# hss-mag-enc-v1.net
KiCad netlist of a schematic drawn in EAGLE
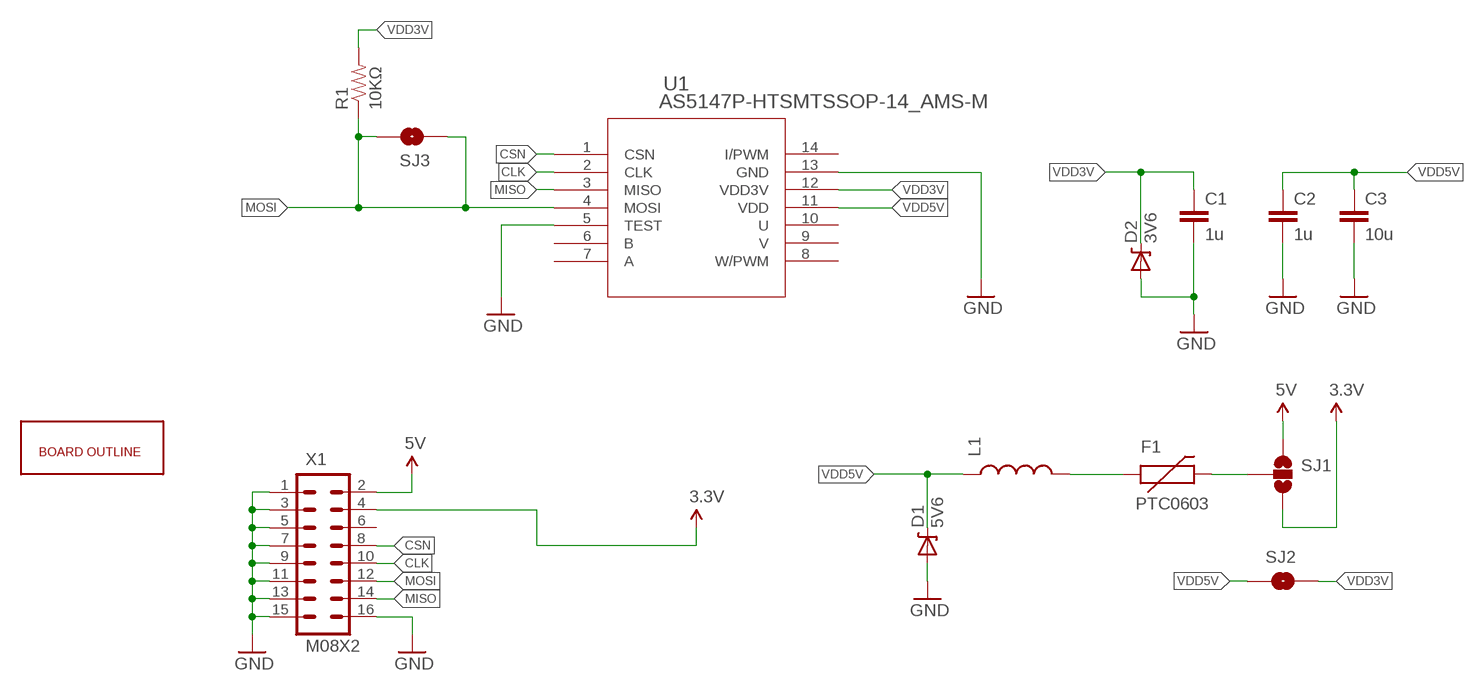
[diagram p0: schematic, sheet 1]

(export (version "E")
  (design (tool "Eeschema 10.0.6"))
  (components
    (comp (ref "C1")
      (value "1u")
      (footprint "eagle-import:0805")
      (libsource (lib "eagle-import") (part "CAP0805"))
    )
    (comp (ref "C2")
      (value "1u")
      (footprint "eagle-import:0805")
      (libsource (lib "eagle-import") (part "CAP0805"))
    )
    (comp (ref "C3")
      (value "10u")
      (footprint "eagle-import:0805")
      (libsource (lib "eagle-import") (part "CAP0805"))
    )
    (comp (ref "D1")
      (value "5V6")
      (footprint "eagle-import:SOD-323")
      (libsource (lib "eagle-import") (part "DIODE-ZENER-BZT52"))
    )
    (comp (ref "D2")
      (value "3V6")
      (footprint "eagle-import:SOD-323")
      (libsource (lib "eagle-import") (part "DIODE-ZENER-BZT52"))
    )
    (comp (ref "F1")
      (value "PTC0603")
      (footprint "eagle-import:0603")
      (libsource (lib "eagle-import") (part "PTC0603"))
    )
    (comp (ref "L1")
      (value "INDUCTOR0805")
      (footprint "eagle-import:0805")
      (libsource (lib "eagle-import") (part "INDUCTOR0805"))
    )
    (comp (ref "R1")
      (value "10KΩ")
      (footprint "eagle-import:0603-RES")
      (libsource (lib "eagle-import") (part "RESISTOR0603-RES"))
    )
    (comp (ref "SJ1")
      (value "SOLDERJUMPER_2WAYS")
      (footprint "eagle-import:SJ_3")
      (libsource (lib "eagle-import") (part "SOLDERJUMPER_2WAYS"))
    )
    (comp (ref "SJ2")
      (value "SOLDERJUMPERNO")
      (footprint "eagle-import:SJ_2S-NO")
      (libsource (lib "eagle-import") (part "SOLDERJUMPERNO"))
    )
    (comp (ref "SJ3")
      (value "SOLDERJUMPERNO")
      (footprint "eagle-import:SJ_2S-NO")
      (libsource (lib "eagle-import") (part "SOLDERJUMPERNO"))
    )
    (comp (ref "U$1")
      (value "BOARD-OUTLINE-V1")
      (footprint "eagle-import:BOARD-OUTLINE")
      (libsource (lib "eagle-import") (part "BOARD-OUTLINE-V1"))
    )
    (comp (ref "U1")
      (value "AS5147P-HTSMTSSOP-14_AMS-M")
      (footprint "eagle-import:TSSOP-14_AMS-M")
      (fields
        (field (name "MANUFACTURER_PART_NUMBER") "AS5147P-HTSM")
        (field (name "COPYRIGHT") "Copyright (C) 2025 Ultra Librarian. All rights reserved.")
      )
      (libsource (lib "eagle-import") (part "AS5147P-HTSMTSSOP-14_AMS-M"))
    )
    (comp (ref "X1")
      (value "M08X2")
      (footprint "eagle-import:2X8")
      (libsource (lib "eagle-import") (part "M08X2"))
    )
  )
  (nets
    (net (code "1") (name "3.3V") (class "Default")
      (node (ref "SJ1") (pin "3") (pinfunction "3_3") (pintype "passive"))
      (node (ref "X1") (pin "4") (pinfunction "4_4") (pintype "passive"))
    )
    (net (code "2") (name "5V") (class "Default")
      (node (ref "SJ1") (pin "1") (pinfunction "1_1") (pintype "passive"))
      (node (ref "X1") (pin "2") (pinfunction "2_2") (pintype "passive"))
    )
    (net (code "3") (name "CLK") (class "Default")
      (node (ref "U1") (pin "2") (pinfunction "CLK_2") (pintype "input"))
      (node (ref "X1") (pin "10") (pinfunction "10_10") (pintype "passive"))
    )
    (net (code "4") (name "CSN") (class "Default")
      (node (ref "U1") (pin "1") (pinfunction "CSN_1") (pintype "input"))
      (node (ref "X1") (pin "8") (pinfunction "8_8") (pintype "passive"))
    )
    (net (code "5") (name "GND") (class "Default")
      (node (ref "C1") (pin "2") (pinfunction "2_2") (pintype "passive"))
      (node (ref "C2") (pin "2") (pinfunction "2_2") (pintype "passive"))
      (node (ref "C3") (pin "2") (pinfunction "2_2") (pintype "passive"))
      (node (ref "D1") (pin "2") (pinfunction "A_2") (pintype "passive"))
      (node (ref "D2") (pin "2") (pinfunction "A_2") (pintype "passive"))
      (node (ref "U1") (pin "13") (pinfunction "GND_13") (pintype "passive"))
      (node (ref "U1") (pin "5") (pinfunction "TEST_5") (pintype "passive"))
      (node (ref "X1") (pin "1") (pinfunction "1_1") (pintype "passive"))
      (node (ref "X1") (pin "11") (pinfunction "11_11") (pintype "passive"))
      (node (ref "X1") (pin "13") (pinfunction "13_13") (pintype "passive"))
      (node (ref "X1") (pin "15") (pinfunction "15_15") (pintype "passive"))
      (node (ref "X1") (pin "16") (pinfunction "16_16") (pintype "passive"))
      (node (ref "X1") (pin "3") (pinfunction "3_3") (pintype "passive"))
      (node (ref "X1") (pin "5") (pinfunction "5_5") (pintype "passive"))
      (node (ref "X1") (pin "7") (pinfunction "7_7") (pintype "passive"))
      (node (ref "X1") (pin "9") (pinfunction "9_9") (pintype "passive"))
    )
    (net (code "6") (name "MISO") (class "Default")
      (node (ref "U1") (pin "3") (pinfunction "MISO_3") (pintype "output"))
      (node (ref "X1") (pin "14") (pinfunction "14_14") (pintype "passive"))
    )
    (net (code "7") (name "MOSI") (class "Default")
      (node (ref "R1") (pin "1") (pinfunction "1_1") (pintype "passive"))
      (node (ref "SJ3") (pin "1") (pinfunction "1_1") (pintype "passive"))
      (node (ref "SJ3") (pin "2") (pinfunction "2_2") (pintype "passive"))
      (node (ref "U1") (pin "4") (pinfunction "MOSI_4") (pintype "input"))
      (node (ref "X1") (pin "12") (pinfunction "12_12") (pintype "passive"))
    )
    (net (code "8") (name "Net-(F1-Pad1)") (class "Default")
      (node (ref "F1") (pin "1") (pinfunction "1_1") (pintype "bidirectional"))
      (node (ref "L1") (pin "2") (pinfunction "2_2") (pintype "passive"))
    )
    (net (code "9") (name "Net-(F1-Pad2)") (class "Default")
      (node (ref "F1") (pin "2") (pinfunction "2_2") (pintype "bidirectional"))
      (node (ref "SJ1") (pin "2") (pinfunction "2_2") (pintype "passive"))
    )
    (net (code "10") (name "VDD3V") (class "Default")
      (node (ref "C1") (pin "1") (pinfunction "1_1") (pintype "passive"))
      (node (ref "D2") (pin "1") (pinfunction "C_1") (pintype "passive"))
      (node (ref "R1") (pin "2") (pinfunction "2_2") (pintype "passive"))
      (node (ref "SJ2") (pin "2") (pinfunction "2_2") (pintype "passive"))
      (node (ref "U1") (pin "12") (pinfunction "VDD3V_12") (pintype "power_in"))
    )
    (net (code "11") (name "VDD5V") (class "Default")
      (node (ref "C2") (pin "1") (pinfunction "1_1") (pintype "passive"))
      (node (ref "C3") (pin "1") (pinfunction "1_1") (pintype "passive"))
      (node (ref "D1") (pin "1") (pinfunction "C_1") (pintype "passive"))
      (node (ref "L1") (pin "1") (pinfunction "1_1") (pintype "passive"))
      (node (ref "SJ2") (pin "1") (pinfunction "1_1") (pintype "passive"))
      (node (ref "U1") (pin "11") (pinfunction "VDD_11") (pintype "power_in"))
    )
    (net (code "12") (name "unconnected-(U1-A-Pad7)") (class "Default")
      (node (ref "U1") (pin "7") (pinfunction "A_7") (pintype "output"))
    )
    (net (code "13") (name "unconnected-(U1-B-Pad6)") (class "Default")
      (node (ref "U1") (pin "6") (pinfunction "B_6") (pintype "output"))
    )
    (net (code "14") (name "unconnected-(U1-I{slash}PWM-Pad14)") (class "Default")
      (node (ref "U1") (pin "14") (pinfunction "I/PWM_14") (pintype "input"))
    )
    (net (code "15") (name "unconnected-(U1-U-Pad10)") (class "Default")
      (node (ref "U1") (pin "10") (pinfunction "U_10") (pintype "output"))
    )
    (net (code "16") (name "unconnected-(U1-V-Pad9)") (class "Default")
      (node (ref "U1") (pin "9") (pinfunction "V_9") (pintype "output"))
    )
    (net (code "17") (name "unconnected-(U1-W{slash}PWM-Pad8)") (class "Default")
      (node (ref "U1") (pin "8") (pinfunction "W/PWM_8") (pintype "output"))
    )
    (net (code "18") (name "unconnected-(X1-Pad6)") (class "Default")
      (node (ref "X1") (pin "6") (pinfunction "6_6") (pintype "passive"))
    )
  )
)
